# thermal.net
KiCad netlist of a schematic drawn in EAGLE
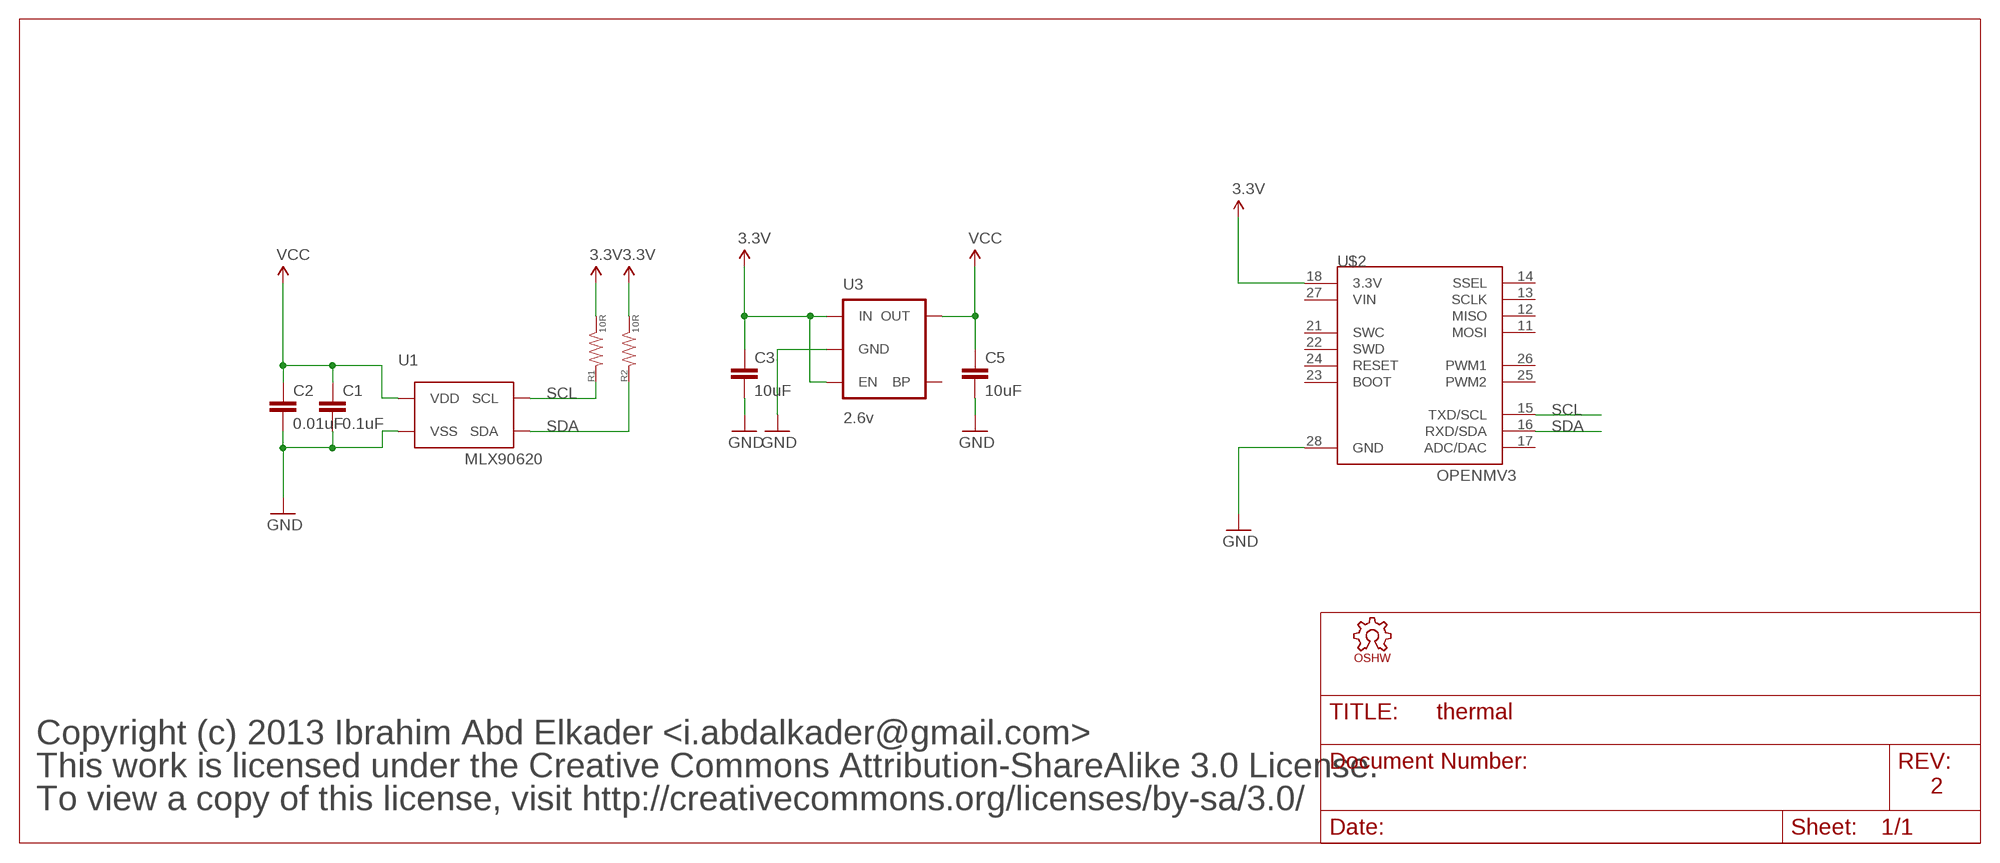
[diagram p0: schematic, sheet 1]

(export (version "E")
  (design (tool "Eeschema 10.0.6"))
  (components
    (comp (ref "C1")
      (value "0.1uF")
      (footprint "eagle-import:0603-CAP")
      (libsource (lib "eagle-import") (part "CAP0603-CAP"))
    )
    (comp (ref "C2")
      (value "0.01uF")
      (footprint "eagle-import:0603-CAP")
      (libsource (lib "eagle-import") (part "CAP0603-CAP"))
    )
    (comp (ref "C3")
      (value "10uF")
      (footprint "eagle-import:0805")
      (libsource (lib "eagle-import") (part "CAP0805"))
    )
    (comp (ref "C5")
      (value "10uF")
      (footprint "eagle-import:0805")
      (libsource (lib "eagle-import") (part "CAP0805"))
    )
    (comp (ref "LOGO1")
      (value "OSHW_LOGO_8MILX0150-NT")
      (footprint "eagle-import:OSHW_8X150_NOTEXT")
      (libsource (lib "eagle-import") (part "OSHW_LOGO_8MILX0150-NT"))
    )
    (comp (ref "R1")
      (value "10R")
      (footprint "eagle-import:0603-RES")
      (libsource (lib "eagle-import") (part "RESISTOR0603-RES"))
    )
    (comp (ref "R2")
      (value "10R")
      (footprint "eagle-import:0603-RES")
      (libsource (lib "eagle-import") (part "RESISTOR0603-RES"))
    )
    (comp (ref "U$2")
      (value "OPENMV3")
      (footprint "eagle-import:OPENMV3")
      (libsource (lib "eagle-import") (part "OPENMV3"))
    )
    (comp (ref "U1")
      (value "MLX90620")
      (footprint "eagle-import:TO39_4")
      (libsource (lib "eagle-import") (part "MLX90620"))
    )
    (comp (ref "U3")
      (value "2.6v")
      (footprint "eagle-import:SOT23-5")
      (libsource (lib "eagle-import") (part "V_REG_LDOSMD"))
    )
  )
  (nets
    (net (code "1") (name "/SCL") (class "Default")
      (node (ref "R1") (pin "2") (pinfunction "2_2") (pintype "passive"))
      (node (ref "U$2") (pin "15") (pinfunction "TXD/SCL_15") (pintype "bidirectional"))
      (node (ref "U1") (pin "1") (pinfunction "SCL_1") (pintype "bidirectional"))
    )
    (net (code "2") (name "/SDA") (class "Default")
      (node (ref "R2") (pin "2") (pinfunction "2_2") (pintype "passive"))
      (node (ref "U$2") (pin "16") (pinfunction "RXD/SDA_16") (pintype "bidirectional"))
      (node (ref "U1") (pin "2") (pinfunction "SDA_2") (pintype "bidirectional"))
    )
    (net (code "3") (name "/VIN") (class "Default")
      (node (ref "U$2") (pin "27") (pinfunction "VIN_27") (pintype "power_in"))
    )
    (net (code "4") (name "3.3V") (class "Default")
      (node (ref "C3") (pin "1") (pinfunction "1_1") (pintype "passive"))
      (node (ref "R1") (pin "1") (pinfunction "1_1") (pintype "passive"))
      (node (ref "R2") (pin "1") (pinfunction "1_1") (pintype "passive"))
      (node (ref "U$2") (pin "18") (pinfunction "3.3V_18") (pintype "power_in"))
      (node (ref "U3") (pin "1") (pinfunction "IN_1") (pintype "input"))
      (node (ref "U3") (pin "3") (pinfunction "EN_3") (pintype "input"))
    )
    (net (code "5") (name "GND") (class "Default")
      (node (ref "C1") (pin "2") (pinfunction "2_2") (pintype "passive"))
      (node (ref "C2") (pin "2") (pinfunction "2_2") (pintype "passive"))
      (node (ref "C3") (pin "2") (pinfunction "2_2") (pintype "passive"))
      (node (ref "C5") (pin "2") (pinfunction "2_2") (pintype "passive"))
      (node (ref "U$2") (pin "28") (pinfunction "GND_28") (pintype "power_in"))
      (node (ref "U1") (pin "4") (pinfunction "VSS_4") (pintype "power_in"))
      (node (ref "U3") (pin "2") (pinfunction "GND_2") (pintype "input"))
    )
    (net (code "6") (name "VCC") (class "Default")
      (node (ref "C1") (pin "1") (pinfunction "1_1") (pintype "passive"))
      (node (ref "C2") (pin "1") (pinfunction "1_1") (pintype "passive"))
      (node (ref "C5") (pin "1") (pinfunction "1_1") (pintype "passive"))
      (node (ref "U1") (pin "3") (pinfunction "VDD_3") (pintype "power_in"))
      (node (ref "U3") (pin "5") (pinfunction "OUT_5") (pintype "passive"))
    )
    (net (code "7") (name "unconnected-(U$2-ADC{slash}DAC-Pad17)") (class "Default")
      (node (ref "U$2") (pin "17") (pinfunction "ADC/DAC_17") (pintype "bidirectional"))
    )
    (net (code "8") (name "unconnected-(U$2-BOOT-Pad23)") (class "Default")
      (node (ref "U$2") (pin "23") (pinfunction "BOOT_23") (pintype "bidirectional"))
    )
    (net (code "9") (name "unconnected-(U$2-MISO-Pad12)") (class "Default")
      (node (ref "U$2") (pin "12") (pinfunction "MISO_12") (pintype "bidirectional"))
    )
    (net (code "10") (name "unconnected-(U$2-MOSI-Pad11)") (class "Default")
      (node (ref "U$2") (pin "11") (pinfunction "MOSI_11") (pintype "bidirectional"))
    )
    (net (code "11") (name "unconnected-(U$2-PWM1-Pad26)") (class "Default")
      (node (ref "U$2") (pin "26") (pinfunction "PWM1_26") (pintype "bidirectional"))
    )
    (net (code "12") (name "unconnected-(U$2-PWM2-Pad25)") (class "Default")
      (node (ref "U$2") (pin "25") (pinfunction "PWM2_25") (pintype "bidirectional"))
    )
    (net (code "13") (name "unconnected-(U$2-RESET-Pad24)") (class "Default")
      (node (ref "U$2") (pin "24") (pinfunction "RESET_24") (pintype "bidirectional"))
    )
    (net (code "14") (name "unconnected-(U$2-SCLK-Pad13)") (class "Default")
      (node (ref "U$2") (pin "13") (pinfunction "SCLK_13") (pintype "bidirectional"))
    )
    (net (code "15") (name "unconnected-(U$2-SSEL-Pad14)") (class "Default")
      (node (ref "U$2") (pin "14") (pinfunction "SSEL_14") (pintype "bidirectional"))
    )
    (net (code "16") (name "unconnected-(U$2-SWC-Pad21)") (class "Default")
      (node (ref "U$2") (pin "21") (pinfunction "SWC_21") (pintype "bidirectional"))
    )
    (net (code "17") (name "unconnected-(U$2-SWD-Pad22)") (class "Default")
      (node (ref "U$2") (pin "22") (pinfunction "SWD_22") (pintype "bidirectional"))
    )
    (net (code "18") (name "unconnected-(U3-BP-Pad4)") (class "Default")
      (node (ref "U3") (pin "4") (pinfunction "BP_4") (pintype "input"))
    )
  )
)
